# basic_schematic.net
KiCad netlist of a schematic drawn in EAGLE
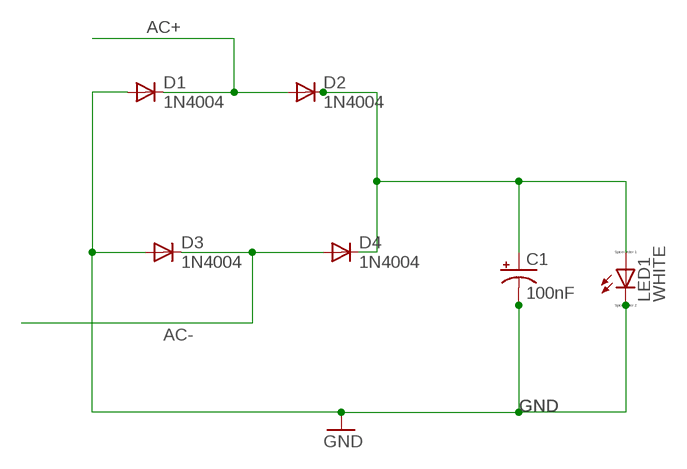
[diagram p0: schematic, sheet 1]

(export (version "E")
  (design (tool "Eeschema 10.0.6"))
  (components
    (comp (ref "C1")
      (value "100nF")
      (footprint "eagle-import:153CLV-1014")
      (libsource (lib "eagle-import") (part "CPOL-US153CLV-1014"))
    )
    (comp (ref "D1")
      (value "1N4004")
      (footprint "eagle-import:DO41-10")
      (libsource (lib "eagle-import") (part "1N4004"))
    )
    (comp (ref "D2")
      (value "1N4004")
      (footprint "eagle-import:DO41-10")
      (libsource (lib "eagle-import") (part "1N4004"))
    )
    (comp (ref "D3")
      (value "1N4004")
      (footprint "eagle-import:DO41-10")
      (libsource (lib "eagle-import") (part "1N4004"))
    )
    (comp (ref "D4")
      (value "1N4004")
      (footprint "eagle-import:DO41-10")
      (libsource (lib "eagle-import") (part "1N4004"))
    )
    (comp (ref "LED1")
      (value "WHITE")
      (footprint "eagle-import:LED_1206")
      (libsource (lib "eagle-import") (part "LED_E"))
    )
  )
  (nets
    (net (code "1") (name "/AC+") (class "Default")
      (node (ref "D1") (pin "C") (pinfunction "C_C") (pintype "passive"))
      (node (ref "D2") (pin "A") (pinfunction "A_A") (pintype "passive"))
    )
    (net (code "2") (name "/AC-") (class "Default")
      (node (ref "D3") (pin "C") (pinfunction "C_C") (pintype "passive"))
      (node (ref "D4") (pin "A") (pinfunction "A_A") (pintype "passive"))
    )
    (net (code "3") (name "GND") (class "Default")
      (node (ref "C1") (pin "-") (pinfunction "-_-") (pintype "passive"))
      (node (ref "D1") (pin "A") (pinfunction "A_A") (pintype "passive"))
      (node (ref "D3") (pin "A") (pinfunction "A_A") (pintype "passive"))
      (node (ref "LED1") (pin "C") (pinfunction "C_C") (pintype "passive"))
    )
    (net (code "4") (name "Net-(C1-Pad+)") (class "Default")
      (node (ref "C1") (pin "+") (pinfunction "+_+") (pintype "passive"))
      (node (ref "D2") (pin "C") (pinfunction "C_C") (pintype "passive"))
      (node (ref "D4") (pin "C") (pinfunction "C_C") (pintype "passive"))
      (node (ref "LED1") (pin "A") (pinfunction "A_A") (pintype "passive"))
    )
  )
)
